# lab_02.net
KiCad netlist of a schematic drawn in EAGLE
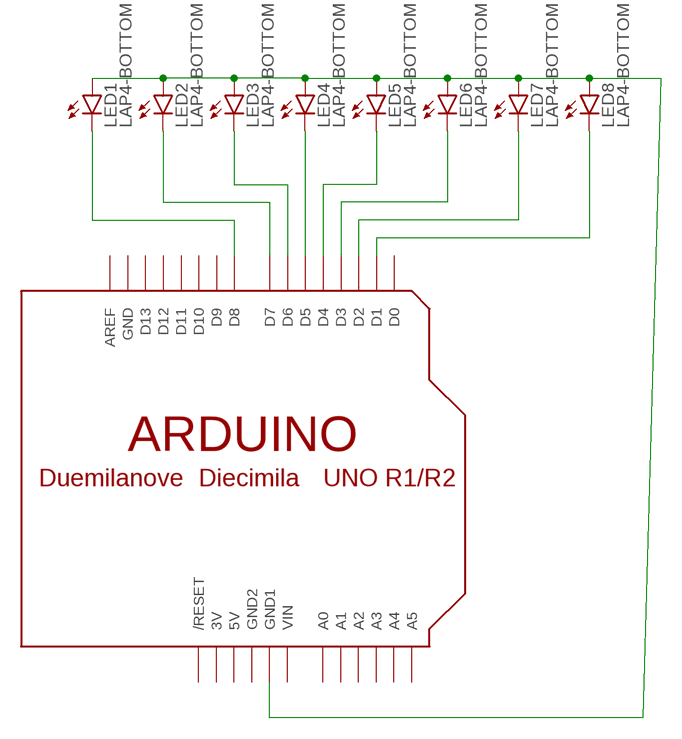
[diagram p0: schematic, sheet 1]

(export (version "E")
  (design (tool "Eeschema 10.0.6"))
  (components
    (comp (ref "LED1")
      (value "LAP4-BOTTOM")
      (footprint "eagle-import:P47F-BOTTOM")
      (libsource (lib "eagle-import") (part "P4-BOTTOMLA"))
    )
    (comp (ref "LED2")
      (value "LAP4-BOTTOM")
      (footprint "eagle-import:P47F-BOTTOM")
      (libsource (lib "eagle-import") (part "P4-BOTTOMLA"))
    )
    (comp (ref "LED3")
      (value "LAP4-BOTTOM")
      (footprint "eagle-import:P47F-BOTTOM")
      (libsource (lib "eagle-import") (part "P4-BOTTOMLA"))
    )
    (comp (ref "LED4")
      (value "LAP4-BOTTOM")
      (footprint "eagle-import:P47F-BOTTOM")
      (libsource (lib "eagle-import") (part "P4-BOTTOMLA"))
    )
    (comp (ref "LED5")
      (value "LAP4-BOTTOM")
      (footprint "eagle-import:P47F-BOTTOM")
      (libsource (lib "eagle-import") (part "P4-BOTTOMLA"))
    )
    (comp (ref "LED6")
      (value "LAP4-BOTTOM")
      (footprint "eagle-import:P47F-BOTTOM")
      (libsource (lib "eagle-import") (part "P4-BOTTOMLA"))
    )
    (comp (ref "LED7")
      (value "LAP4-BOTTOM")
      (footprint "eagle-import:P47F-BOTTOM")
      (libsource (lib "eagle-import") (part "P4-BOTTOMLA"))
    )
    (comp (ref "LED8")
      (value "LAP4-BOTTOM")
      (footprint "eagle-import:P47F-BOTTOM")
      (libsource (lib "eagle-import") (part "P4-BOTTOMLA"))
    )
    (comp (ref "U$1")
      (value "ARDUINO-BPLACE")
      (footprint "eagle-import:ARDUINO-BPLACE")
      (libsource (lib "eagle-import") (part "ARDUINO-BPLACE"))
    )
  )
  (nets
    (net (code "1") (name "/3V") (class "Default")
      (node (ref "U$1") (pin "3V") (pinfunction "3V_3V") (pintype "power_in"))
    )
    (net (code "2") (name "/5V") (class "Default")
      (node (ref "U$1") (pin "5V") (pinfunction "5V_5V") (pintype "power_in"))
    )
    (net (code "3") (name "/GND") (class "Default")
      (node (ref "U$1") (pin "GND") (pinfunction "GND_GND") (pintype "power_in"))
    )
    (net (code "4") (name "/GND2") (class "Default")
      (node (ref "U$1") (pin "GND2") (pinfunction "GND2_GND2") (pintype "power_in"))
    )
    (net (code "5") (name "/VIN") (class "Default")
      (node (ref "U$1") (pin "VIN") (pinfunction "VIN_VIN") (pintype "power_in"))
    )
    (net (code "6") (name "Net-(LED1-PadA)") (class "Default")
      (node (ref "LED1") (pin "A") (pinfunction "A_A") (pintype "passive"))
      (node (ref "LED2") (pin "A") (pinfunction "A_A") (pintype "passive"))
      (node (ref "LED3") (pin "A") (pinfunction "A_A") (pintype "passive"))
      (node (ref "LED4") (pin "A") (pinfunction "A_A") (pintype "passive"))
      (node (ref "LED5") (pin "A") (pinfunction "A_A") (pintype "passive"))
      (node (ref "LED6") (pin "A") (pinfunction "A_A") (pintype "passive"))
      (node (ref "LED7") (pin "A") (pinfunction "A_A") (pintype "passive"))
      (node (ref "LED8") (pin "A") (pinfunction "A_A") (pintype "passive"))
      (node (ref "U$1") (pin "GND1") (pinfunction "GND1_GND1") (pintype "power_in"))
    )
    (net (code "7") (name "Net-(LED1-PadC)") (class "Default")
      (node (ref "LED1") (pin "C") (pinfunction "C_C") (pintype "passive"))
      (node (ref "U$1") (pin "D8") (pinfunction "D8_D8") (pintype "bidirectional"))
    )
    (net (code "8") (name "Net-(LED2-PadC)") (class "Default")
      (node (ref "LED2") (pin "C") (pinfunction "C_C") (pintype "passive"))
      (node (ref "U$1") (pin "D7") (pinfunction "D7_D7") (pintype "bidirectional"))
    )
    (net (code "9") (name "Net-(LED3-PadC)") (class "Default")
      (node (ref "LED3") (pin "C") (pinfunction "C_C") (pintype "passive"))
      (node (ref "U$1") (pin "D6") (pinfunction "D6_D6") (pintype "bidirectional"))
    )
    (net (code "10") (name "Net-(LED4-PadC)") (class "Default")
      (node (ref "LED4") (pin "C") (pinfunction "C_C") (pintype "passive"))
      (node (ref "U$1") (pin "D5") (pinfunction "D5_D5") (pintype "bidirectional"))
    )
    (net (code "11") (name "Net-(LED5-PadC)") (class "Default")
      (node (ref "LED5") (pin "C") (pinfunction "C_C") (pintype "passive"))
      (node (ref "U$1") (pin "D4") (pinfunction "D4_D4") (pintype "bidirectional"))
    )
    (net (code "12") (name "Net-(LED6-PadC)") (class "Default")
      (node (ref "LED6") (pin "C") (pinfunction "C_C") (pintype "passive"))
      (node (ref "U$1") (pin "D3") (pinfunction "D3_D3") (pintype "bidirectional"))
    )
    (net (code "13") (name "Net-(LED7-PadC)") (class "Default")
      (node (ref "LED7") (pin "C") (pinfunction "C_C") (pintype "passive"))
      (node (ref "U$1") (pin "D2") (pinfunction "D2_D2") (pintype "bidirectional"))
    )
    (net (code "14") (name "Net-(LED8-PadC)") (class "Default")
      (node (ref "LED8") (pin "C") (pinfunction "C_C") (pintype "passive"))
      (node (ref "U$1") (pin "D1") (pinfunction "D1_D1") (pintype "bidirectional"))
    )
    (net (code "15") (name "unconnected-(U$1-PadA0)") (class "Default")
      (node (ref "U$1") (pin "A0") (pinfunction "A0_A0") (pintype "bidirectional"))
    )
    (net (code "16") (name "unconnected-(U$1-PadA1)") (class "Default")
      (node (ref "U$1") (pin "A1") (pinfunction "A1_A1") (pintype "bidirectional"))
    )
    (net (code "17") (name "unconnected-(U$1-PadA2)") (class "Default")
      (node (ref "U$1") (pin "A2") (pinfunction "A2_A2") (pintype "bidirectional"))
    )
    (net (code "18") (name "unconnected-(U$1-PadA3)") (class "Default")
      (node (ref "U$1") (pin "A3") (pinfunction "A3_A3") (pintype "bidirectional"))
    )
    (net (code "19") (name "unconnected-(U$1-PadA4)") (class "Default")
      (node (ref "U$1") (pin "A4") (pinfunction "A4_A4") (pintype "bidirectional"))
    )
    (net (code "20") (name "unconnected-(U$1-PadA5)") (class "Default")
      (node (ref "U$1") (pin "A5") (pinfunction "A5_A5") (pintype "bidirectional"))
    )
    (net (code "21") (name "unconnected-(U$1-PadAREF)") (class "Default")
      (node (ref "U$1") (pin "AREF") (pinfunction "AREF_AREF") (pintype "bidirectional"))
    )
    (net (code "22") (name "unconnected-(U$1-PadD0)") (class "Default")
      (node (ref "U$1") (pin "D0") (pinfunction "D0_D0") (pintype "bidirectional"))
    )
    (net (code "23") (name "unconnected-(U$1-PadD9)") (class "Default")
      (node (ref "U$1") (pin "D9") (pinfunction "D9_D9") (pintype "bidirectional"))
    )
    (net (code "24") (name "unconnected-(U$1-PadD10)") (class "Default")
      (node (ref "U$1") (pin "D10") (pinfunction "D10_D10") (pintype "bidirectional"))
    )
    (net (code "25") (name "unconnected-(U$1-PadD11)") (class "Default")
      (node (ref "U$1") (pin "D11") (pinfunction "D11_D11") (pintype "bidirectional"))
    )
    (net (code "26") (name "unconnected-(U$1-PadD12)") (class "Default")
      (node (ref "U$1") (pin "D12") (pinfunction "D12_D12") (pintype "bidirectional"))
    )
    (net (code "27") (name "unconnected-(U$1-PadD13)") (class "Default")
      (node (ref "U$1") (pin "D13") (pinfunction "D13_D13") (pintype "bidirectional"))
    )
    (net (code "28") (name "unconnected-(U$1-{slash}RESET-PadRESET)") (class "Default")
      (node (ref "U$1") (pin "RESET") (pinfunction "/RESET_RESET") (pintype "bidirectional"))
    )
  )
)
